# 05_USB.net
KiCad netlist of a schematic drawn in Altium Designer
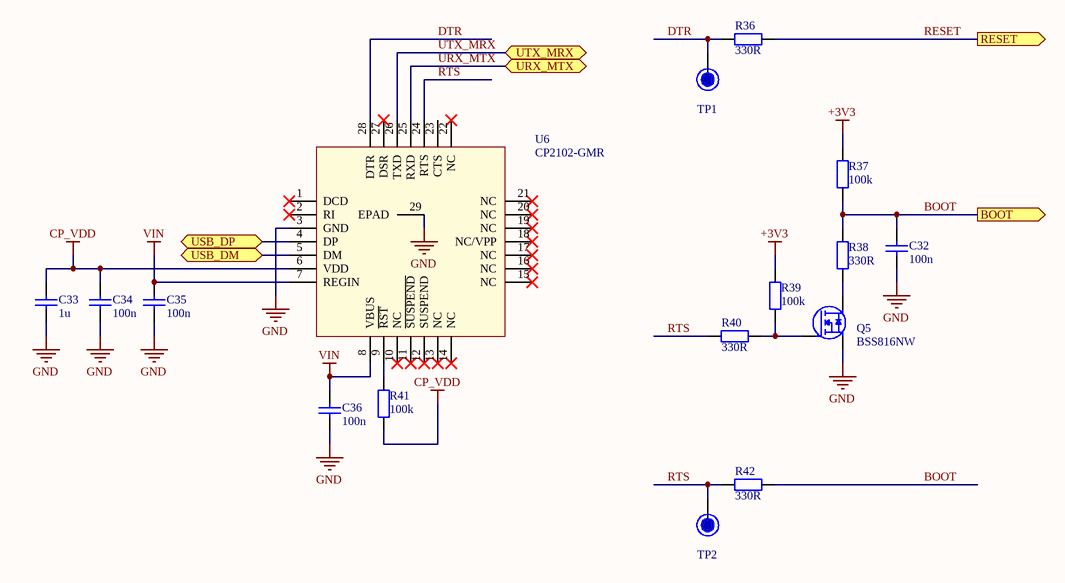
[diagram p0: 05_USB.SchDoc]

(export (version "E")
  (design (tool "Eeschema 10.0.6"))
  (components
    (comp (ref "C32")
      (value "100n")
      (footprint "C0603_IPC_MD")
      (description "CAP CER 0.1UF 16V X7R 0603")
      (fields
        (field (name "MANUFACTURER") "Samsung Electro-Mechanics")
        (field (name "MANUFACTURER PART NUMBER") "CL10B104KO8NNNC")
      )
      (libsource (lib "alfasat_parts_lib") (part "CL10B104KO8NNNC"))
    )
    (comp (ref "C33")
      (value "1u")
      (footprint "C0603_IPC_MD")
      (description "CAP CER 1UF 16V X7R 0603")
      (fields
        (field (name "MANUFACTURER") "Samsung Electro-Mechanics")
        (field (name "MANUFACTURER PART NUMBER") "CL10B105MO8NNWC")
      )
      (libsource (lib "alfasat_parts_lib") (part "CL10B105MO8NNWC"))
    )
    (comp (ref "C34")
      (value "100n")
      (footprint "C0603_IPC_MD")
      (description "CAP CER 0.1UF 16V X7R 0603")
      (fields
        (field (name "MANUFACTURER") "Samsung Electro-Mechanics")
        (field (name "MANUFACTURER PART NUMBER") "CL10B104KO8NNNC")
      )
      (libsource (lib "alfasat_lib") (part "CL10B104KO8NNNC"))
    )
    (comp (ref "C35")
      (value "100n")
      (footprint "C0603_IPC_MD")
      (description "CAP CER 0.1UF 16V X7R 0603")
      (fields
        (field (name "MANUFACTURER") "Samsung Electro-Mechanics")
        (field (name "MANUFACTURER PART NUMBER") "CL10B104KO8NNNC")
      )
      (libsource (lib "alfasat_lib") (part "CL10B104KO8NNNC"))
    )
    (comp (ref "C36")
      (value "100n")
      (footprint "C0603_IPC_MD")
      (description "CAP CER 0.1UF 16V X7R 0603")
      (fields
        (field (name "MANUFACTURER") "Samsung Electro-Mechanics")
        (field (name "MANUFACTURER PART NUMBER") "CL10B104KO8NNNC")
      )
      (libsource (lib "alfasat_lib") (part "CL10B104KO8NNNC"))
    )
    (comp (ref "Q5")
      (value "BSS816NW")
      (footprint "SOT323")
      (description "N-Channel Logic Level Enhancement Mode Field Effect Transistor")
      (fields (field (name "MANUFACTURER") "Infineon Technologies"))
      (libsource (lib "alfasat_parts_lib") (part "BSS816"))
    )
    (comp (ref "R36")
      (value "330R")
      (footprint "R0603_IPC_MD")
      (description "RES SMD 330 OHM 5% 1/10W 0603")
      (fields
        (field (name "MANUFACTURER") "Bourns Inc.")
        (field (name "MANUFACTURER PART NUMBER") "CR0603-JW-331ELF")
      )
      (libsource (lib "alfasat_parts_lib") (part "CR0603-JW-331ELF"))
    )
    (comp (ref "R37")
      (value "100k")
      (footprint "R0603_IPC_MD")
      (description "RES 100K OHM 1% 1/10W 0603")
      (fields
        (field (name "MANUFACTURER") "Bourns Inc.")
        (field (name "MANUFACTURER PART NUMBER") "RMCF0603FT100K")
      )
      (libsource (lib "alfasat_parts_lib") (part "RMCF0603FT100K"))
    )
    (comp (ref "R38")
      (value "330R")
      (footprint "R0603_IPC_MD")
      (description "RES SMD 330 OHM 5% 1/10W 0603")
      (fields
        (field (name "MANUFACTURER") "Bourns Inc.")
        (field (name "MANUFACTURER PART NUMBER") "CR0603-JW-331ELF")
      )
      (libsource (lib "") (part "CR0603-JW-331ELF_2"))
    )
    (comp (ref "R39")
      (value "100k")
      (footprint "R0603_IPC_MD")
      (description "RES 100K OHM 1% 1/10W 0603")
      (fields
        (field (name "MANUFACTURER") "Bourns Inc.")
        (field (name "MANUFACTURER PART NUMBER") "RMCF0603FT100K")
      )
      (libsource (lib "alfasat_parts_lib") (part "RMCF0603FT100K"))
    )
    (comp (ref "R40")
      (value "330R")
      (footprint "R0603_IPC_MD")
      (description "RES SMD 330 OHM 5% 1/10W 0603")
      (fields
        (field (name "MANUFACTURER") "Bourns Inc.")
        (field (name "MANUFACTURER PART NUMBER") "CR0603-JW-331ELF")
      )
      (libsource (lib "") (part "CR0603-JW-331ELF_1"))
    )
    (comp (ref "R41")
      (value "100k")
      (footprint "R0603_IPC_MD")
      (description "RES 100K OHM 1% 1/10W 0603")
      (fields
        (field (name "MANUFACTURER") "Bourns Inc.")
        (field (name "MANUFACTURER PART NUMBER") "RMCF0603FT100K")
      )
      (libsource (lib "alfasat_lib") (part "RMCF0603FT100K"))
    )
    (comp (ref "R42")
      (value "330R")
      (footprint "R0603_IPC_MD")
      (description "RES SMD 330 OHM 5% 1/10W 0603")
      (fields
        (field (name "MANUFACTURER") "Bourns Inc.")
        (field (name "MANUFACTURER PART NUMBER") "CR0603-JW-331ELF")
      )
      (libsource (lib "") (part "CR0603-JW-331ELF_1"))
    )
    (comp (ref "TP1")
      (value "RTS")
      (footprint "TestPoint_1M5")
      (description "Test Point")
      (libsource (lib "alfasat_parts_lib") (part "TP"))
    )
    (comp (ref "TP2")
      (value "DTR")
      (footprint "TestPoint_1M5")
      (description "Test Point")
      (libsource (lib "alfasat_parts_lib") (part "TP"))
    )
    (comp (ref "U6")
      (value "CP2102-GMR")
      (footprint "QFN28_(SL)")
      (description "IC USB-TO-UART BRIDGE 28VQFN")
      (fields (field (name "MANUFACTURER") "Silicon Labs"))
      (libsource (lib "alfasat_lib") (part "CP2102-GMR"))
    )
  )
  (nets
    (net (code "1") (name "+3V3") (class "Default")
      (node (ref "R37") (pin "2") (pinfunction "2_2") (pintype "passive"))
      (node (ref "R39") (pin "2") (pinfunction "2_2") (pintype "passive"))
    )
    (net (code "2") (name "/BOOT") (class "Default")
      (node (ref "C32") (pin "2") (pinfunction "2_2") (pintype "passive"))
      (node (ref "R37") (pin "1") (pinfunction "1_1") (pintype "passive"))
      (node (ref "R38") (pin "1") (pinfunction "1_1") (pintype "passive"))
      (node (ref "R42") (pin "2") (pinfunction "2_2") (pintype "passive"))
    )
    (net (code "3") (name "/DTR") (class "Default")
      (node (ref "R36") (pin "2") (pinfunction "2_2") (pintype "passive"))
      (node (ref "TP1") (pin "0") (pinfunction "0_0") (pintype "passive"))
      (node (ref "U6") (pin "28") (pinfunction "DTR_28") (pintype "passive"))
    )
    (net (code "4") (name "/RESET") (class "Default")
      (node (ref "R36") (pin "1") (pinfunction "1_1") (pintype "passive"))
    )
    (net (code "5") (name "/RTS") (class "Default")
      (node (ref "R40") (pin "1") (pinfunction "1_1") (pintype "passive"))
      (node (ref "R42") (pin "1") (pinfunction "1_1") (pintype "passive"))
      (node (ref "TP2") (pin "0") (pinfunction "0_0") (pintype "passive"))
      (node (ref "U6") (pin "24") (pinfunction "RTS_24") (pintype "passive"))
    )
    (net (code "6") (name "/URX_MTX") (class "Default")
      (node (ref "U6") (pin "25") (pinfunction "RXD_25") (pintype "passive"))
    )
    (net (code "7") (name "/USB_DM") (class "Default")
      (node (ref "U6") (pin "5") (pinfunction "DM_5") (pintype "passive"))
    )
    (net (code "8") (name "/USB_DP") (class "Default")
      (node (ref "U6") (pin "4") (pinfunction "DP_4") (pintype "passive"))
    )
    (net (code "9") (name "/UTX_MRX") (class "Default")
      (node (ref "U6") (pin "26") (pinfunction "TXD_26") (pintype "passive"))
    )
    (net (code "10") (name "CP_VDD") (class "Default")
      (node (ref "C33") (pin "2") (pinfunction "2_2") (pintype "passive"))
      (node (ref "C34") (pin "2") (pinfunction "2_2") (pintype "passive"))
      (node (ref "R41") (pin "1") (pinfunction "1_1") (pintype "passive"))
      (node (ref "U6") (pin "6") (pinfunction "VDD_6") (pintype "passive"))
    )
    (net (code "11") (name "GND") (class "Default")
      (node (ref "C32") (pin "1") (pinfunction "1_1") (pintype "passive"))
      (node (ref "C33") (pin "1") (pinfunction "1_1") (pintype "passive"))
      (node (ref "C34") (pin "1") (pinfunction "1_1") (pintype "passive"))
      (node (ref "C35") (pin "1") (pinfunction "1_1") (pintype "passive"))
      (node (ref "C36") (pin "1") (pinfunction "1_1") (pintype "passive"))
      (node (ref "Q5") (pin "2") (pinfunction "S_2") (pintype "passive"))
      (node (ref "U6") (pin "29") (pinfunction "EPAD_29") (pintype "passive"))
      (node (ref "U6") (pin "3") (pinfunction "GND_3") (pintype "passive"))
    )
    (net (code "12") (name "Net-(Q5-D)") (class "Default")
      (node (ref "Q5") (pin "3") (pinfunction "D_3") (pintype "passive"))
      (node (ref "R38") (pin "2") (pinfunction "2_2") (pintype "passive"))
    )
    (net (code "13") (name "Net-(Q5-G)") (class "Default")
      (node (ref "Q5") (pin "1") (pinfunction "G_1") (pintype "passive"))
      (node (ref "R39") (pin "1") (pinfunction "1_1") (pintype "passive"))
      (node (ref "R40") (pin "2") (pinfunction "2_2") (pintype "passive"))
    )
    (net (code "14") (name "Net-(U6-~{RST})") (class "Default")
      (node (ref "R41") (pin "2") (pinfunction "2_2") (pintype "passive"))
      (node (ref "U6") (pin "9") (pinfunction "~{RST}_9") (pintype "passive"))
    )
    (net (code "15") (name "VIN") (class "Default")
      (node (ref "C35") (pin "2") (pinfunction "2_2") (pintype "passive"))
      (node (ref "C36") (pin "2") (pinfunction "2_2") (pintype "passive"))
      (node (ref "U6") (pin "7") (pinfunction "REGIN_7") (pintype "passive"))
      (node (ref "U6") (pin "8") (pinfunction "VBUS_8") (pintype "passive"))
    )
    (net (code "16") (name "unconnected-(U6-CTS-Pad23)") (class "Default")
      (node (ref "U6") (pin "23") (pinfunction "CTS_23") (pintype "passive"))
    )
    (net (code "17") (name "unconnected-(U6-DCD-Pad1)") (class "Default")
      (node (ref "U6") (pin "1") (pinfunction "DCD_1") (pintype "passive+no_connect"))
    )
    (net (code "18") (name "unconnected-(U6-DSR-Pad27)") (class "Default")
      (node (ref "U6") (pin "27") (pinfunction "DSR_27") (pintype "passive+no_connect"))
    )
    (net (code "19") (name "unconnected-(U6-NC-Pad10)") (class "Default")
      (node (ref "U6") (pin "10") (pinfunction "NC_10") (pintype "passive+no_connect"))
    )
    (net (code "20") (name "unconnected-(U6-NC-Pad13)") (class "Default")
      (node (ref "U6") (pin "13") (pinfunction "NC_13") (pintype "passive+no_connect"))
    )
    (net (code "21") (name "unconnected-(U6-NC-Pad14)") (class "Default")
      (node (ref "U6") (pin "14") (pinfunction "NC_14") (pintype "passive+no_connect"))
    )
    (net (code "22") (name "unconnected-(U6-NC-Pad15)") (class "Default")
      (node (ref "U6") (pin "15") (pinfunction "NC_15") (pintype "passive+no_connect"))
    )
    (net (code "23") (name "unconnected-(U6-NC-Pad16)") (class "Default")
      (node (ref "U6") (pin "16") (pinfunction "NC_16") (pintype "passive+no_connect"))
    )
    (net (code "24") (name "unconnected-(U6-NC-Pad17)") (class "Default")
      (node (ref "U6") (pin "17") (pinfunction "NC_17") (pintype "passive+no_connect"))
    )
    (net (code "25") (name "unconnected-(U6-NC-Pad19)") (class "Default")
      (node (ref "U6") (pin "19") (pinfunction "NC_19") (pintype "passive+no_connect"))
    )
    (net (code "26") (name "unconnected-(U6-NC-Pad20)") (class "Default")
      (node (ref "U6") (pin "20") (pinfunction "NC_20") (pintype "passive+no_connect"))
    )
    (net (code "27") (name "unconnected-(U6-NC-Pad21)") (class "Default")
      (node (ref "U6") (pin "21") (pinfunction "NC_21") (pintype "passive+no_connect"))
    )
    (net (code "28") (name "unconnected-(U6-NC-Pad22)") (class "Default")
      (node (ref "U6") (pin "22") (pinfunction "NC_22") (pintype "passive+no_connect"))
    )
    (net (code "29") (name "unconnected-(U6-NC{slash}VPP-Pad18)") (class "Default")
      (node (ref "U6") (pin "18") (pinfunction "NC/VPP_18") (pintype "passive+no_connect"))
    )
    (net (code "30") (name "unconnected-(U6-RI-Pad2)") (class "Default")
      (node (ref "U6") (pin "2") (pinfunction "RI_2") (pintype "passive+no_connect"))
    )
    (net (code "31") (name "unconnected-(U6-SUSPEND-Pad12)") (class "Default")
      (node (ref "U6") (pin "12") (pinfunction "SUSPEND_12") (pintype "passive+no_connect"))
    )
    (net (code "32") (name "unconnected-(U6-~{SUSPEND}-Pad11)") (class "Default")
      (node (ref "U6") (pin "11") (pinfunction "~{SUSPEND}_11") (pintype "passive+no_connect"))
    )
  )
)
